# Power.net
KiCad netlist of a schematic drawn in Altium Designer
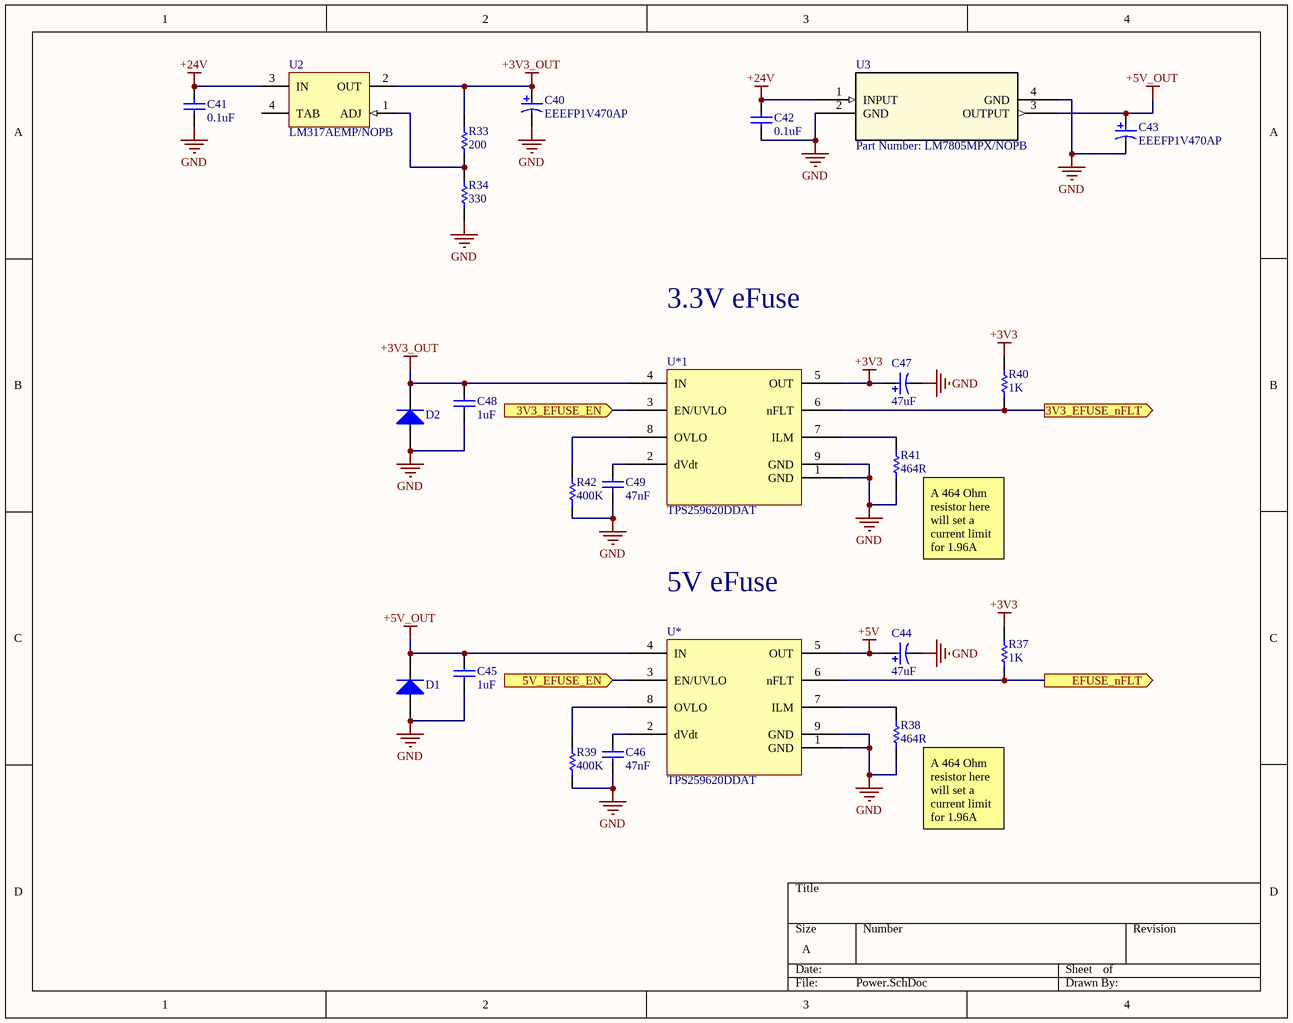
[diagram p0: Power.SchDoc]

(export (version "E")
  (design (tool "Eeschema 10.0.6"))
  (components
    (comp (ref "C40")
      (value "EEEFP1V470AP")
      (footprint "PNSC-FP-V-D_V")
      (fields (field (name "MANUFACTURER") "Panasonic"))
      (libsource (lib "Altium Content Vault") (part "CAP-P-2"))
    )
    (comp (ref "C41")
      (value "0.1uF")
      (footprint "CAPC1608X90X35ML10T15")
      (description "Chip Capacitor, 0.1 uF, +/- 10%, 50 V, -55 to 125 degC, 0603 (1608 Metric), RoHS, Tape and Reel")
      (fields (field (name "TOLERANCE") "10%") (field (name "VOLTAGE") "50V"))
      (libsource (lib "Altium Content Vault") (part "CAP-NP-2"))
    )
    (comp (ref "C42")
      (value "0.1uF")
      (footprint "CAPC1608X90X35ML10T15")
      (description "Chip Capacitor, 0.1 uF, +/- 10%, 50 V, -55 to 125 degC, 0603 (1608 Metric), RoHS, Tape and Reel")
      (fields (field (name "TOLERANCE") "10%") (field (name "VOLTAGE") "50V"))
      (libsource (lib "Altium Content Vault") (part "CAP-NP-2"))
    )
    (comp (ref "C43")
      (value "EEEFP1V470AP")
      (footprint "PNSC-FP-V-D_V")
      (fields (field (name "MANUFACTURER") "Panasonic"))
      (libsource (lib "Altium Content Vault") (part "CAP-P-2"))
    )
    (comp (ref "C44")
      (value "47uF")
      (footprint "PNSC-FP-V-D_V")
      (fields (field (name "MANUFACTURER") "Panasonic"))
      (libsource (lib "Altium Content Vault") (part "CAP-P-2"))
    )
    (comp (ref "C45")
      (value "1uF")
      (footprint "CAPC1608X90X20LL10")
      (description "Chip Capacitor, 1 uF, +/- 10%, 50 V, -55 to 85 degC, 0603 (1608 Metric), RoHS, Tape and Reel")
      (fields
        (field (name "MANUFACTURER") "TDK")
        (field (name "PCN PART NUMBER") "MLCCPartNumberChange30/Nov/2012")
      )
      (libsource (lib "Altium Content Vault") (part "CAP-NP-2"))
    )
    (comp (ref "C46")
      (value "47nF")
      (footprint "CAPC1608X90X35ML10T15")
      (fields (field (name "MANUFACTURER") "Murata") (field (name "PART NUMBER") "GRM188R71H473KA61D"))
      (libsource (lib "Altium Content Vault") (part "CAP"))
    )
    (comp (ref "C47")
      (value "47uF")
      (footprint "PNSC-FP-V-D_V")
      (fields (field (name "MANUFACTURER") "Panasonic"))
      (libsource (lib "Altium Content Vault") (part "CAP-P-2"))
    )
    (comp (ref "C48")
      (value "1uF")
      (footprint "CAPC1608X90X20LL10")
      (description "Chip Capacitor, 1 uF, +/- 10%, 50 V, -55 to 85 degC, 0603 (1608 Metric), RoHS, Tape and Reel")
      (fields
        (field (name "MANUFACTURER") "TDK")
        (field (name "PCN PART NUMBER") "MLCCPartNumberChange30/Nov/2012")
      )
      (libsource (lib "Altium Content Vault") (part "CAP-NP-2"))
    )
    (comp (ref "C49")
      (value "47nF")
      (footprint "CAPC1608X90X35ML10T15")
      (fields (field (name "MANUFACTURER") "Murata") (field (name "PART NUMBER") "GRM188R71H473KA61D"))
      (libsource (lib "Altium Content Vault") (part "CAP"))
    )
    (comp (ref "D1")
      (value "SMAJ5.0A-E3/61")
      (footprint "VISH-DO-214AC-2_M")
      (fields (field (name "MANUFACTURER") "Vishay Semiconductor"))
      (libsource (lib "Altium Content Vault") (part "VISH-K1A2-2"))
    )
    (comp (ref "D2")
      (value "SMAJ5.0A-E3/61")
      (footprint "VISH-DO-214AC-2_M")
      (fields (field (name "MANUFACTURER") "Vishay Semiconductor"))
      (libsource (lib "Altium Content Vault") (part "VISH-K1A2-2"))
    )
    (comp (ref "R33")
      (value "200")
      (footprint "RESC1608X55X30NL20T20")
      (fields (field (name "MANUFACTURER") "Panasonic") (field (name "PART NUMBER") "ERA3AEB201V"))
      (libsource (lib "Altium Content Vault") (part "RES"))
    )
    (comp (ref "R34")
      (value "330")
      (footprint "RESC1608X55X30NL15T15")
      (fields (field (name "PART NUMBER") "ERJ3EKF3300V") (field (name "MANUFACTURER") "Panasonic"))
      (libsource (lib "Altium Content Vault") (part "RES"))
    )
    (comp (ref "R37")
      (value "1K")
      (footprint "RESC1608X55X30LL15T15")
      (fields (field (name "MANUFACTURER") "Panasonic") (field (name "PART NUMBER") "ERJ-3EKF3000V"))
      (libsource (lib "Altium Content Vault") (part "RES"))
    )
    (comp (ref "R38")
      (value "464R")
      (footprint "RESC1608X55X30LL15T15")
      (fields (field (name "MANUFACTURER") "Panasonic") (field (name "PART NUMBER") "ERJ-3EKF3000V"))
      (libsource (lib "Altium Content Vault") (part "RES"))
    )
    (comp (ref "R39")
      (value "400K")
      (footprint "RESC1608X55X30LL15T15")
      (fields (field (name "MANUFACTURER") "Panasonic") (field (name "PART NUMBER") "ERJ-3EKF3000V"))
      (libsource (lib "Altium Content Vault") (part "RES"))
    )
    (comp (ref "R40")
      (value "1K")
      (footprint "RESC1608X55X30LL15T15")
      (fields (field (name "MANUFACTURER") "Panasonic") (field (name "PART NUMBER") "ERJ-3EKF3000V"))
      (libsource (lib "Altium Content Vault") (part "RES"))
    )
    (comp (ref "R41")
      (value "464R")
      (footprint "RESC1608X55X30LL15T15")
      (fields (field (name "MANUFACTURER") "Panasonic") (field (name "PART NUMBER") "ERJ-3EKF3000V"))
      (libsource (lib "Altium Content Vault") (part "RES"))
    )
    (comp (ref "R42")
      (value "400K")
      (footprint "RESC1608X55X30LL15T15")
      (fields (field (name "MANUFACTURER") "Panasonic") (field (name "PART NUMBER") "ERJ-3EKF3000V"))
      (libsource (lib "Altium Content Vault") (part "RES"))
    )
    (comp (ref "U*") (value "TPS259620DDAT") (libsource (lib "TI_TPS259629DDAT") (part "TPS259620DDAT")))
    (comp (ref "U*1") (value "TPS259620DDAT") (libsource (lib "TI_TPS259629DDAT") (part "TPS259620DDAT")))
    (comp (ref "U2")
      (value "LM317AEMP/NOPB")
      (footprint "DCY0004A_L")
      (description "3-Terminal Adjustable Regulator, 4-pin SOT-223, Pb-Free")
      (fields (field (name "MANUFACTURER") "Texas Instruments"))
      (libsource (lib "Altium Content Vault") (part "PM-REG-LM317ADJ-SOT4"))
    )
    (comp (ref "U3")
      (value "Part Number: LM7805MPX/NOPB")
      (footprint "DCY4")
      (description "No Description Available")
      (fields
        (field (name "MANUFACTURER_PART_NUMBER") "LM7805MPX/NOPB")
        (field (name "COPYRIGHT") "Copyright (C) 2018 Accelerated Designs. All rights reserved")
      )
      (libsource (lib "Capstone_IFFF") (part "LM7805MPX/NOPB"))
    )
  )
  (nets
    (net (code "1") (name "+3V3") (class "Default")
      (node (ref "C47") (pin "1") (pinfunction "1_1") (pintype "passive"))
      (node (ref "R37") (pin "2") (pinfunction "2_2") (pintype "passive"))
      (node (ref "R40") (pin "2") (pinfunction "2_2") (pintype "passive"))
      (node (ref "U*1") (pin "5") (pinfunction "OUT_5") (pintype "passive"))
    )
    (net (code "2") (name "+3V3_OUT") (class "Default")
      (node (ref "C40") (pin "1") (pinfunction "1_1") (pintype "passive"))
      (node (ref "C48") (pin "2") (pinfunction "2_2") (pintype "passive"))
      (node (ref "D2") (pin "1") (pinfunction "K_1") (pintype "passive"))
      (node (ref "R33") (pin "2") (pinfunction "2_2") (pintype "passive"))
      (node (ref "U*1") (pin "4") (pinfunction "IN_4") (pintype "passive"))
      (node (ref "U2") (pin "2") (pinfunction "OUT_2") (pintype "power_in"))
    )
    (net (code "3") (name "+5V") (class "Default")
      (node (ref "C44") (pin "1") (pinfunction "1_1") (pintype "passive"))
      (node (ref "U*") (pin "5") (pinfunction "OUT_5") (pintype "passive"))
    )
    (net (code "4") (name "+5V_OUT") (class "Default")
      (node (ref "C43") (pin "1") (pinfunction "1_1") (pintype "passive"))
      (node (ref "C45") (pin "2") (pinfunction "2_2") (pintype "passive"))
      (node (ref "D1") (pin "1") (pinfunction "K_1") (pintype "passive"))
      (node (ref "U*") (pin "4") (pinfunction "IN_4") (pintype "passive"))
      (node (ref "U3") (pin "3") (pinfunction "OUTPUT_3") (pintype "output"))
    )
    (net (code "5") (name "+24V") (class "Default")
      (node (ref "C41") (pin "2") (pinfunction "2_2") (pintype "passive"))
      (node (ref "C42") (pin "2") (pinfunction "2_2") (pintype "passive"))
      (node (ref "U2") (pin "3") (pinfunction "IN_3") (pintype "power_in"))
      (node (ref "U3") (pin "1") (pinfunction "INPUT_1") (pintype "input"))
    )
    (net (code "6") (name "/3V3_EFUSE_EN") (class "Default")
      (node (ref "U*1") (pin "3") (pinfunction "EN/UVLO_3") (pintype "passive"))
    )
    (net (code "7") (name "/3V3_EFUSE_nFLT") (class "Default")
      (node (ref "R40") (pin "1") (pinfunction "1_1") (pintype "passive"))
      (node (ref "U*1") (pin "6") (pinfunction "nFLT_6") (pintype "passive"))
    )
    (net (code "8") (name "/5V_EFUSE_EN") (class "Default")
      (node (ref "U*") (pin "3") (pinfunction "EN/UVLO_3") (pintype "passive"))
    )
    (net (code "9") (name "/EFUSE_nFLT") (class "Default")
      (node (ref "R37") (pin "1") (pinfunction "1_1") (pintype "passive"))
      (node (ref "U*") (pin "6") (pinfunction "nFLT_6") (pintype "passive"))
    )
    (net (code "10") (name "GND") (class "Default")
      (node (ref "C40") (pin "2") (pinfunction "2_2") (pintype "passive"))
      (node (ref "C41") (pin "1") (pinfunction "1_1") (pintype "passive"))
      (node (ref "C42") (pin "1") (pinfunction "1_1") (pintype "passive"))
      (node (ref "C43") (pin "2") (pinfunction "2_2") (pintype "passive"))
      (node (ref "C44") (pin "2") (pinfunction "2_2") (pintype "passive"))
      (node (ref "C45") (pin "1") (pinfunction "1_1") (pintype "passive"))
      (node (ref "C46") (pin "1") (pinfunction "1_1") (pintype "passive"))
      (node (ref "C47") (pin "2") (pinfunction "2_2") (pintype "passive"))
      (node (ref "C48") (pin "1") (pinfunction "1_1") (pintype "passive"))
      (node (ref "C49") (pin "1") (pinfunction "1_1") (pintype "passive"))
      (node (ref "D1") (pin "2") (pinfunction "A_2") (pintype "passive"))
      (node (ref "D2") (pin "2") (pinfunction "A_2") (pintype "passive"))
      (node (ref "R34") (pin "1") (pinfunction "1_1") (pintype "passive"))
      (node (ref "R38") (pin "1") (pinfunction "1_1") (pintype "passive"))
      (node (ref "R39") (pin "1") (pinfunction "1_1") (pintype "passive"))
      (node (ref "R41") (pin "1") (pinfunction "1_1") (pintype "passive"))
      (node (ref "R42") (pin "1") (pinfunction "1_1") (pintype "passive"))
      (node (ref "U*") (pin "1") (pinfunction "GND_1") (pintype "passive"))
      (node (ref "U*") (pin "9") (pinfunction "GND_9") (pintype "passive"))
      (node (ref "U*1") (pin "1") (pinfunction "GND_1") (pintype "passive"))
      (node (ref "U*1") (pin "9") (pinfunction "GND_9") (pintype "passive"))
      (node (ref "U3") (pin "2") (pinfunction "GND_2") (pintype "power_in"))
      (node (ref "U3") (pin "4") (pinfunction "GND_4") (pintype "power_in"))
    )
    (net (code "11") (name "Net-(U*-ILM)") (class "Default")
      (node (ref "R38") (pin "2") (pinfunction "2_2") (pintype "passive"))
      (node (ref "U*") (pin "7") (pinfunction "ILM_7") (pintype "passive"))
    )
    (net (code "12") (name "Net-(U*-OVLO)") (class "Default")
      (node (ref "R39") (pin "2") (pinfunction "2_2") (pintype "passive"))
      (node (ref "U*") (pin "8") (pinfunction "OVLO_8") (pintype "passive"))
    )
    (net (code "13") (name "Net-(U*-dVdt)") (class "Default")
      (node (ref "C46") (pin "2") (pinfunction "2_2") (pintype "passive"))
      (node (ref "U*") (pin "2") (pinfunction "dVdt_2") (pintype "passive"))
    )
    (net (code "14") (name "Net-(U*1-ILM)") (class "Default")
      (node (ref "R41") (pin "2") (pinfunction "2_2") (pintype "passive"))
      (node (ref "U*1") (pin "7") (pinfunction "ILM_7") (pintype "passive"))
    )
    (net (code "15") (name "Net-(U*1-OVLO)") (class "Default")
      (node (ref "R42") (pin "2") (pinfunction "2_2") (pintype "passive"))
      (node (ref "U*1") (pin "8") (pinfunction "OVLO_8") (pintype "passive"))
    )
    (net (code "16") (name "Net-(U*1-dVdt)") (class "Default")
      (node (ref "C49") (pin "2") (pinfunction "2_2") (pintype "passive"))
      (node (ref "U*1") (pin "2") (pinfunction "dVdt_2") (pintype "passive"))
    )
    (net (code "17") (name "Net-(U2-ADJ)") (class "Default")
      (node (ref "R33") (pin "1") (pinfunction "1_1") (pintype "passive"))
      (node (ref "R34") (pin "2") (pinfunction "2_2") (pintype "passive"))
      (node (ref "U2") (pin "1") (pinfunction "ADJ_1") (pintype "input"))
    )
    (net (code "18") (name "unconnected-(U2-TAB-Pad4)") (class "Default")
      (node (ref "U2") (pin "4") (pinfunction "TAB_4") (pintype "power_in"))
    )
  )
)
